# Power.net
KiCad netlist of a schematic drawn in Altium Designer
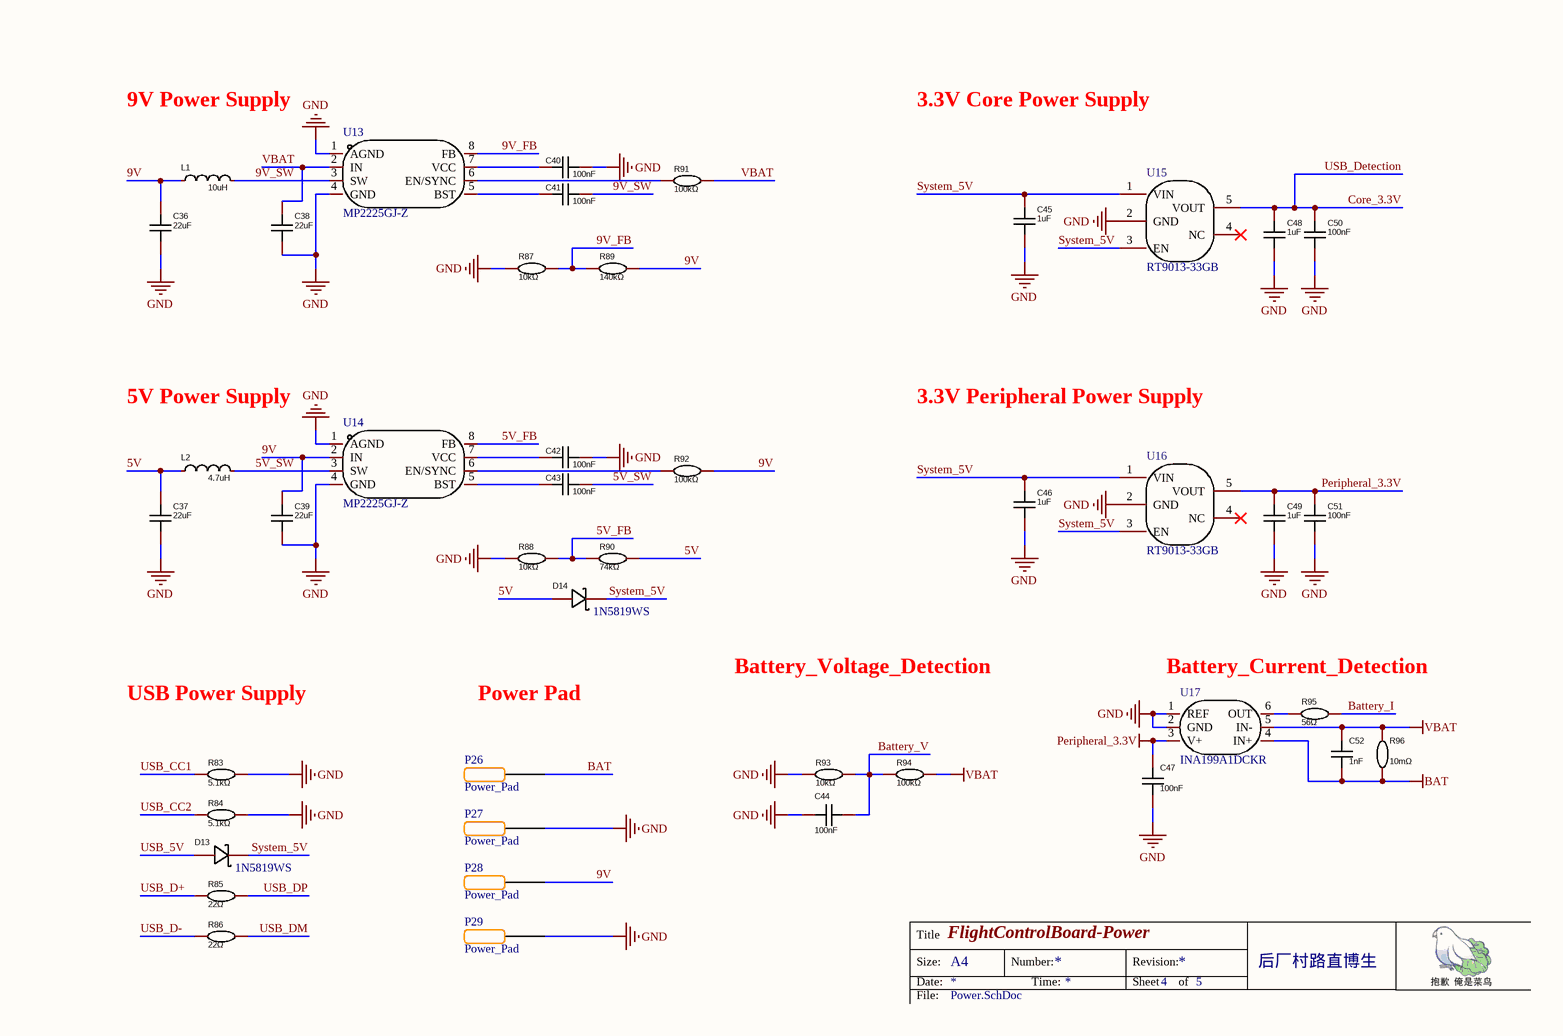
[diagram p0: Power.SchDoc]

(export (version "E")
  (design (tool "Eeschema 10.0.6"))
  (components
    (comp (ref "C36")
      (value "22uF")
      (footprint "C0603")
      (libsource (lib "Capacitor") (part "CC0603KRX7R9BB104"))
    )
    (comp (ref "C37")
      (value "22uF")
      (footprint "C0603")
      (libsource (lib "Capacitor") (part "CC0603KRX7R9BB104"))
    )
    (comp (ref "C38")
      (value "22uF")
      (footprint "C0603")
      (libsource (lib "Capacitor") (part "CC0603KRX7R9BB104"))
    )
    (comp (ref "C39")
      (value "22uF")
      (footprint "C0603")
      (libsource (lib "Capacitor") (part "CC0603KRX7R9BB104"))
    )
    (comp (ref "C40")
      (value "100nF")
      (footprint "C0201")
      (libsource (lib "Capacitor") (part "CC0603KRX7R9BB104"))
    )
    (comp (ref "C41")
      (value "100nF")
      (footprint "C0201")
      (libsource (lib "Capacitor") (part "CC0603KRX7R9BB104"))
    )
    (comp (ref "C42")
      (value "100nF")
      (footprint "C0201")
      (libsource (lib "Capacitor") (part "CC0603KRX7R9BB104"))
    )
    (comp (ref "C43")
      (value "100nF")
      (footprint "C0201")
      (libsource (lib "Capacitor") (part "CC0603KRX7R9BB104"))
    )
    (comp (ref "C44")
      (value "100nF")
      (footprint "C0201")
      (libsource (lib "Capacitor") (part "CC0603KRX7R9BB104"))
    )
    (comp (ref "C45")
      (value "1uF")
      (footprint "C0402")
      (libsource (lib "Capacitor") (part "CC0603KRX7R9BB104"))
    )
    (comp (ref "C46")
      (value "1uF")
      (footprint "C0402")
      (libsource (lib "Capacitor") (part "CC0603KRX7R9BB104"))
    )
    (comp (ref "C47")
      (value "100nF")
      (footprint "C0201")
      (libsource (lib "Capacitor") (part "CC0603KRX7R9BB104"))
    )
    (comp (ref "C48")
      (value "1uF")
      (footprint "C0402")
      (libsource (lib "Capacitor") (part "CC0603KRX7R9BB104"))
    )
    (comp (ref "C49")
      (value "1uF")
      (footprint "C0402")
      (libsource (lib "Capacitor") (part "CC0603KRX7R9BB104"))
    )
    (comp (ref "C50")
      (value "100nF")
      (footprint "C0201")
      (libsource (lib "Capacitor") (part "CC0603KRX7R9BB104"))
    )
    (comp (ref "C51")
      (value "100nF")
      (footprint "C0201")
      (libsource (lib "Capacitor") (part "CC0603KRX7R9BB104"))
    )
    (comp (ref "C52")
      (value "1nF")
      (footprint "C0201")
      (libsource (lib "Capacitor") (part "CC0603KRX7R9BB104"))
    )
    (comp (ref "D13")
      (value "1N5819WS")
      (footprint "SOD-323")
      (fields (field (name "MANUFACTURER") "Hottech(合科泰)"))
      (libsource (lib "Diode") (part "1N5819WS"))
    )
    (comp (ref "D14")
      (value "1N5819WS")
      (footprint "SOD-323")
      (fields (field (name "MANUFACTURER") "Hottech(合科泰)"))
      (libsource (lib "Diode") (part "1N5819WS"))
    )
    (comp (ref "L1")
      (value "10uH")
      (footprint "IND-SMD_L4.0-W4.0")
      (fields
        (field (name "MANUFACTURER") "cjiang(长江微电)")
        (field (name "MANUFACTURER PART") "FHD4020S-100MT")
        (field (name "TOLERANCE") "±10%")
      )
      (libsource (lib "Inductor") (part "SDFL2012T220KTF"))
    )
    (comp (ref "L2")
      (value "4.7uH")
      (footprint "IND-SMD_L4.0-W4.0")
      (fields
        (field (name "MANUFACTURER") "cjiang(长江微电)")
        (field (name "MANUFACTURER PART") "FHD4020S-4R7MT")
        (field (name "TOLERANCE") "±10%")
      )
      (libsource (lib "Inductor") (part "SDFL2012T220KTF"))
    )
    (comp (ref "P26")
      (value "Power_Pad")
      (footprint "POWER HALF HOLE")
      (libsource (lib "Pad") (part "Power_Pad"))
    )
    (comp (ref "P27")
      (value "Power_Pad")
      (footprint "POWER HALF HOLE")
      (libsource (lib "Pad") (part "Power_Pad"))
    )
    (comp (ref "P28")
      (value "Power_Pad")
      (footprint "POWER HALF HOLE")
      (libsource (lib "Pad") (part "Power_Pad"))
    )
    (comp (ref "P29")
      (value "Power_Pad")
      (footprint "POWER HALF HOLE")
      (libsource (lib "Pad") (part "Power_Pad"))
    )
    (comp (ref "R83")
      (value "5.1kΩ")
      (footprint "R0201")
      (libsource (lib "Resistor") (part "0603WAF1002T5E"))
    )
    (comp (ref "R84")
      (value "5.1kΩ")
      (footprint "R0201")
      (libsource (lib "Resistor") (part "0603WAF1002T5E"))
    )
    (comp (ref "R85") (value "22Ω") (footprint "R0201") (libsource (lib "Resistor") (part "0603WAF1002T5E")))
    (comp (ref "R86") (value "22Ω") (footprint "R0201") (libsource (lib "Resistor") (part "0603WAF1002T5E")))
    (comp (ref "R87") (value "10kΩ") (footprint "R0201") (libsource (lib "Resistor") (part "0603WAF1002T5E")))
    (comp (ref "R88") (value "10kΩ") (footprint "R0201") (libsource (lib "Resistor") (part "0603WAF1002T5E")))
    (comp (ref "R89")
      (value "140kΩ")
      (footprint "R0201")
      (libsource (lib "Resistor") (part "0603WAF1002T5E"))
    )
    (comp (ref "R90") (value "74kΩ") (footprint "R0201") (libsource (lib "Resistor") (part "0603WAF1002T5E")))
    (comp (ref "R91")
      (value "100kΩ")
      (footprint "R0201")
      (libsource (lib "Resistor") (part "0603WAF1002T5E"))
    )
    (comp (ref "R92")
      (value "100kΩ")
      (footprint "R0201")
      (libsource (lib "Resistor") (part "0603WAF1002T5E"))
    )
    (comp (ref "R93") (value "10kΩ") (footprint "R0201") (libsource (lib "Resistor") (part "0603WAF1002T5E")))
    (comp (ref "R94")
      (value "100kΩ")
      (footprint "R0201")
      (libsource (lib "Resistor") (part "0603WAF1002T5E"))
    )
    (comp (ref "R95") (value "56Ω") (footprint "R0201") (libsource (lib "Resistor") (part "0603WAF1002T5E")))
    (comp (ref "R96") (value "10mΩ") (footprint "R0805") (libsource (lib "Resistor") (part "0603WAF1002T5E")))
    (comp (ref "U13")
      (value "MP2225GJ-Z")
      (footprint "SOT-23-8")
      (libsource (lib "Power") (part "MP2225GJ-Z"))
    )
    (comp (ref "U14")
      (value "MP2225GJ-Z")
      (footprint "SOT-23-8")
      (libsource (lib "Power") (part "MP2225GJ-Z"))
    )
    (comp (ref "U15")
      (value "RT9013-33GB")
      (footprint "SOT-23-5")
      (fields (field (name "MANUFACTURER") "RICHTEK(立锜)"))
      (libsource (lib "Power") (part "RT9013-33GB"))
    )
    (comp (ref "U16")
      (value "RT9013-33GB")
      (footprint "SOT-23-5")
      (fields (field (name "MANUFACTURER") "RICHTEK(立锜)"))
      (libsource (lib "Power") (part "RT9013-33GB"))
    )
    (comp (ref "U17")
      (value "INA199A1DCKR")
      (footprint "SOT-323-6")
      (fields (field (name "MANUFACTURER") "TI(德州仪器)"))
      (libsource (lib "ESC_Drive") (part "INA199A1DCKR"))
    )
  )
  (nets
    (net (code "1") (name "/5V") (class "Default")
      (node (ref "C37") (pin "1") (pinfunction "1_1") (pintype "passive"))
      (node (ref "D14") (pin "2") (pinfunction "A_2") (pintype "passive"))
      (node (ref "L2") (pin "1") (pinfunction "1_1") (pintype "passive"))
      (node (ref "R90") (pin "2") (pinfunction "2_2") (pintype "passive"))
    )
    (net (code "2") (name "/5V_FB") (class "Default")
      (node (ref "R88") (pin "2") (pinfunction "2_2") (pintype "passive"))
      (node (ref "R90") (pin "1") (pinfunction "1_1") (pintype "passive"))
      (node (ref "U14") (pin "8") (pinfunction "FB_8") (pintype "passive"))
    )
    (net (code "3") (name "/5V_SW") (class "Default")
      (node (ref "C43") (pin "1") (pinfunction "1_1") (pintype "passive"))
      (node (ref "L2") (pin "2") (pinfunction "2_2") (pintype "passive"))
      (node (ref "U14") (pin "3") (pinfunction "SW_3") (pintype "passive"))
    )
    (net (code "4") (name "/9V") (class "Default")
      (node (ref "C36") (pin "1") (pinfunction "1_1") (pintype "passive"))
      (node (ref "C39") (pin "1") (pinfunction "1_1") (pintype "passive"))
      (node (ref "L1") (pin "1") (pinfunction "1_1") (pintype "passive"))
      (node (ref "P28") (pin "1") (pinfunction "1_1") (pintype "passive"))
      (node (ref "R89") (pin "2") (pinfunction "2_2") (pintype "passive"))
      (node (ref "R92") (pin "2") (pinfunction "2_2") (pintype "passive"))
      (node (ref "U14") (pin "2") (pinfunction "IN_2") (pintype "passive"))
    )
    (net (code "5") (name "/9V_FB") (class "Default")
      (node (ref "R87") (pin "2") (pinfunction "2_2") (pintype "passive"))
      (node (ref "R89") (pin "1") (pinfunction "1_1") (pintype "passive"))
      (node (ref "U13") (pin "8") (pinfunction "FB_8") (pintype "passive"))
    )
    (net (code "6") (name "/9V_SW") (class "Default")
      (node (ref "C41") (pin "1") (pinfunction "1_1") (pintype "passive"))
      (node (ref "L1") (pin "2") (pinfunction "2_2") (pintype "passive"))
      (node (ref "U13") (pin "3") (pinfunction "SW_3") (pintype "passive"))
    )
    (net (code "7") (name "/Battery_I") (class "Default")
      (node (ref "R95") (pin "2") (pinfunction "2_2") (pintype "passive"))
    )
    (net (code "8") (name "/Battery_V") (class "Default")
      (node (ref "C44") (pin "1") (pinfunction "1_1") (pintype "passive"))
      (node (ref "R93") (pin "2") (pinfunction "2_2") (pintype "passive"))
      (node (ref "R94") (pin "1") (pinfunction "1_1") (pintype "passive"))
    )
    (net (code "9") (name "/Core_3.3V") (class "Default")
      (node (ref "C48") (pin "1") (pinfunction "1_1") (pintype "passive"))
      (node (ref "C50") (pin "1") (pinfunction "1_1") (pintype "passive"))
      (node (ref "U15") (pin "5") (pinfunction "VOUT_5") (pintype "passive"))
    )
    (net (code "10") (name "/System_5V") (class "Default")
      (node (ref "C45") (pin "1") (pinfunction "1_1") (pintype "passive"))
      (node (ref "C46") (pin "1") (pinfunction "1_1") (pintype "passive"))
      (node (ref "D13") (pin "1") (pinfunction "K_1") (pintype "passive"))
      (node (ref "D14") (pin "1") (pinfunction "K_1") (pintype "passive"))
      (node (ref "U15") (pin "1") (pinfunction "VIN_1") (pintype "passive"))
      (node (ref "U15") (pin "3") (pinfunction "EN_3") (pintype "passive"))
      (node (ref "U16") (pin "1") (pinfunction "VIN_1") (pintype "passive"))
      (node (ref "U16") (pin "3") (pinfunction "EN_3") (pintype "passive"))
    )
    (net (code "11") (name "/USB_5V") (class "Default")
      (node (ref "D13") (pin "2") (pinfunction "A_2") (pintype "passive"))
    )
    (net (code "12") (name "/USB_CC1") (class "Default")
      (node (ref "R83") (pin "2") (pinfunction "2_2") (pintype "passive"))
    )
    (net (code "13") (name "/USB_CC2") (class "Default")
      (node (ref "R84") (pin "1") (pinfunction "1_1") (pintype "passive"))
    )
    (net (code "14") (name "/USB_D+") (class "Default")
      (node (ref "R85") (pin "1") (pinfunction "1_1") (pintype "passive"))
    )
    (net (code "15") (name "/USB_D-") (class "Default")
      (node (ref "R86") (pin "1") (pinfunction "1_1") (pintype "passive"))
    )
    (net (code "16") (name "/USB_DM") (class "Default")
      (node (ref "R86") (pin "2") (pinfunction "2_2") (pintype "passive"))
    )
    (net (code "17") (name "/USB_DP") (class "Default")
      (node (ref "R85") (pin "2") (pinfunction "2_2") (pintype "passive"))
    )
    (net (code "18") (name "BAT") (class "Default")
      (node (ref "C52") (pin "2") (pinfunction "2_2") (pintype "passive"))
      (node (ref "P26") (pin "1") (pinfunction "1_1") (pintype "passive"))
      (node (ref "R96") (pin "1") (pinfunction "1_1") (pintype "passive"))
      (node (ref "U17") (pin "4") (pinfunction "IN+_4") (pintype "passive"))
    )
    (net (code "19") (name "GND") (class "Default")
      (node (ref "C36") (pin "2") (pinfunction "2_2") (pintype "passive"))
      (node (ref "C37") (pin "2") (pinfunction "2_2") (pintype "passive"))
      (node (ref "C38") (pin "2") (pinfunction "2_2") (pintype "passive"))
      (node (ref "C39") (pin "2") (pinfunction "2_2") (pintype "passive"))
      (node (ref "C40") (pin "1") (pinfunction "1_1") (pintype "passive"))
      (node (ref "C42") (pin "1") (pinfunction "1_1") (pintype "passive"))
      (node (ref "C44") (pin "2") (pinfunction "2_2") (pintype "passive"))
      (node (ref "C45") (pin "2") (pinfunction "2_2") (pintype "passive"))
      (node (ref "C46") (pin "2") (pinfunction "2_2") (pintype "passive"))
      (node (ref "C47") (pin "2") (pinfunction "2_2") (pintype "passive"))
      (node (ref "C48") (pin "2") (pinfunction "2_2") (pintype "passive"))
      (node (ref "C49") (pin "2") (pinfunction "2_2") (pintype "passive"))
      (node (ref "C50") (pin "2") (pinfunction "2_2") (pintype "passive"))
      (node (ref "C51") (pin "2") (pinfunction "2_2") (pintype "passive"))
      (node (ref "P27") (pin "1") (pinfunction "1_1") (pintype "passive"))
      (node (ref "P29") (pin "1") (pinfunction "1_1") (pintype "passive"))
      (node (ref "R83") (pin "1") (pinfunction "1_1") (pintype "passive"))
      (node (ref "R84") (pin "2") (pinfunction "2_2") (pintype "passive"))
      (node (ref "R87") (pin "1") (pinfunction "1_1") (pintype "passive"))
      (node (ref "R88") (pin "1") (pinfunction "1_1") (pintype "passive"))
      (node (ref "R93") (pin "1") (pinfunction "1_1") (pintype "passive"))
      (node (ref "U13") (pin "1") (pinfunction "AGND_1") (pintype "passive"))
      (node (ref "U13") (pin "4") (pinfunction "GND_4") (pintype "passive"))
      (node (ref "U14") (pin "1") (pinfunction "AGND_1") (pintype "passive"))
      (node (ref "U14") (pin "4") (pinfunction "GND_4") (pintype "passive"))
      (node (ref "U15") (pin "2") (pinfunction "GND_2") (pintype "passive"))
      (node (ref "U16") (pin "2") (pinfunction "GND_2") (pintype "passive"))
      (node (ref "U17") (pin "1") (pinfunction "REF_1") (pintype "passive"))
      (node (ref "U17") (pin "2") (pinfunction "GND_2") (pintype "passive"))
    )
    (net (code "20") (name "Net-(U13-BST)") (class "Default")
      (node (ref "C41") (pin "2") (pinfunction "2_2") (pintype "passive"))
      (node (ref "U13") (pin "5") (pinfunction "BST_5") (pintype "passive"))
    )
    (net (code "21") (name "Net-(U13-EN{slash}SYNC)") (class "Default")
      (node (ref "R91") (pin "1") (pinfunction "1_1") (pintype "passive"))
      (node (ref "U13") (pin "6") (pinfunction "EN/SYNC_6") (pintype "passive"))
    )
    (net (code "22") (name "Net-(U13-VCC)") (class "Default")
      (node (ref "C40") (pin "2") (pinfunction "2_2") (pintype "passive"))
      (node (ref "U13") (pin "7") (pinfunction "VCC_7") (pintype "passive"))
    )
    (net (code "23") (name "Net-(U14-BST)") (class "Default")
      (node (ref "C43") (pin "2") (pinfunction "2_2") (pintype "passive"))
      (node (ref "U14") (pin "5") (pinfunction "BST_5") (pintype "passive"))
    )
    (net (code "24") (name "Net-(U14-EN{slash}SYNC)") (class "Default")
      (node (ref "R92") (pin "1") (pinfunction "1_1") (pintype "passive"))
      (node (ref "U14") (pin "6") (pinfunction "EN/SYNC_6") (pintype "passive"))
    )
    (net (code "25") (name "Net-(U14-VCC)") (class "Default")
      (node (ref "C42") (pin "2") (pinfunction "2_2") (pintype "passive"))
      (node (ref "U14") (pin "7") (pinfunction "VCC_7") (pintype "passive"))
    )
    (net (code "26") (name "Net-(U17-OUT)") (class "Default")
      (node (ref "R95") (pin "1") (pinfunction "1_1") (pintype "passive"))
      (node (ref "U17") (pin "6") (pinfunction "OUT_6") (pintype "passive"))
    )
    (net (code "27") (name "Peripheral_3.3V") (class "Default")
      (node (ref "C47") (pin "1") (pinfunction "1_1") (pintype "passive"))
      (node (ref "C49") (pin "1") (pinfunction "1_1") (pintype "passive"))
      (node (ref "C51") (pin "1") (pinfunction "1_1") (pintype "passive"))
      (node (ref "U16") (pin "5") (pinfunction "VOUT_5") (pintype "passive"))
      (node (ref "U17") (pin "3") (pinfunction "V+_3") (pintype "passive"))
    )
    (net (code "28") (name "VBAT") (class "Default")
      (node (ref "C38") (pin "1") (pinfunction "1_1") (pintype "passive"))
      (node (ref "C52") (pin "1") (pinfunction "1_1") (pintype "passive"))
      (node (ref "R91") (pin "2") (pinfunction "2_2") (pintype "passive"))
      (node (ref "R94") (pin "2") (pinfunction "2_2") (pintype "passive"))
      (node (ref "R96") (pin "2") (pinfunction "2_2") (pintype "passive"))
      (node (ref "U13") (pin "2") (pinfunction "IN_2") (pintype "passive"))
      (node (ref "U17") (pin "5") (pinfunction "IN-_5") (pintype "passive"))
    )
    (net (code "29") (name "unconnected-(U15-NC-Pad4)") (class "Default")
      (node (ref "U15") (pin "4") (pinfunction "NC_4") (pintype "passive+no_connect"))
    )
    (net (code "30") (name "unconnected-(U16-NC-Pad4)") (class "Default")
      (node (ref "U16") (pin "4") (pinfunction "NC_4") (pintype "passive+no_connect"))
    )
  )
)
